# rapidshark-lipo-sensor-mk-3_2.net
KiCad netlist of a schematic drawn in EAGLE
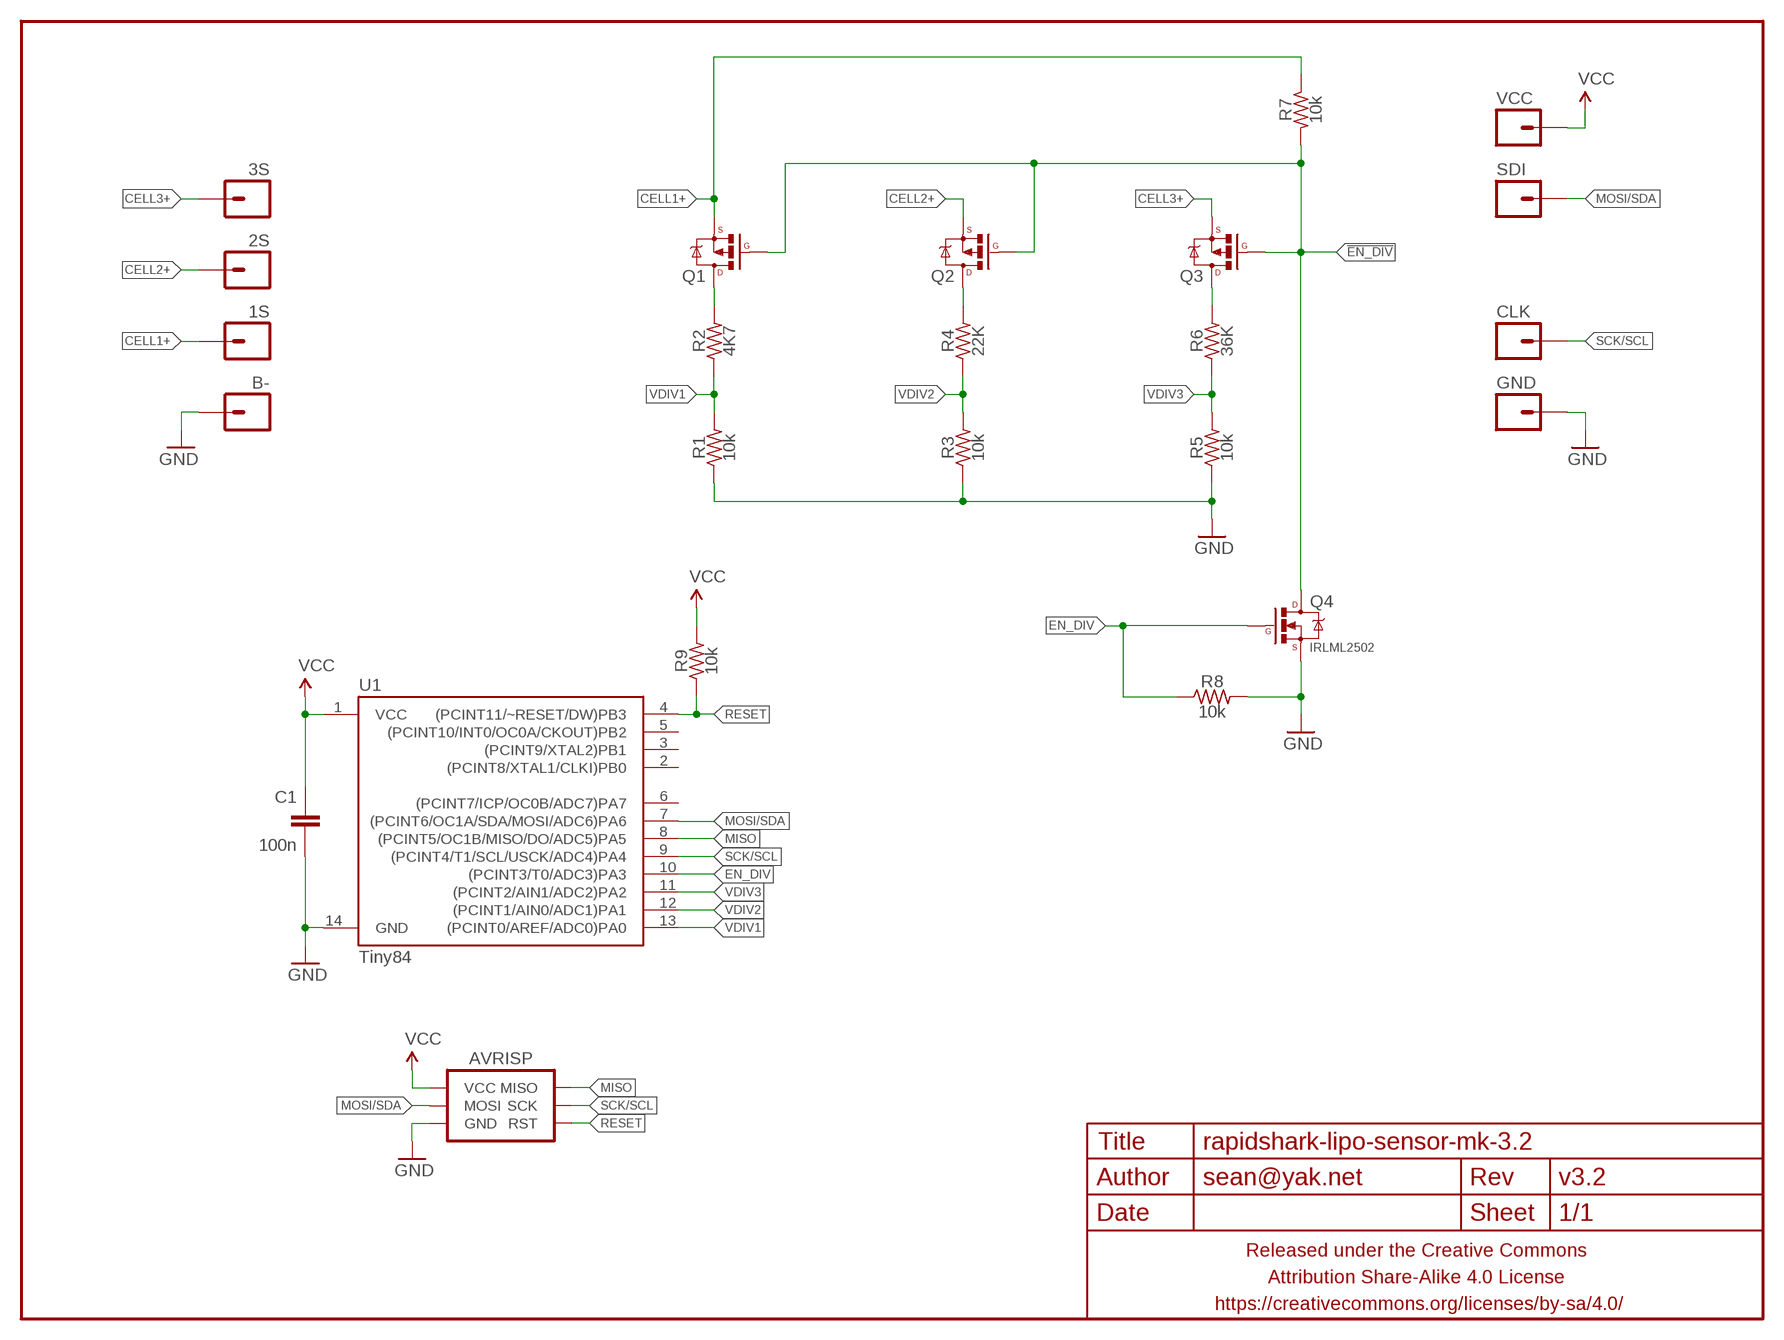
[diagram p0: schematic, sheet 1]

(export (version "E")
  (design (tool "Eeschema 10.0.6"))
  (components
    (comp (ref "1S")
      (value "M01PTH-0.9MM")
      (footprint "eagle-import:1X01-0.9MM")
      (libsource (lib "eagle-import") (part "M01PTH-0.9MM"))
    )
    (comp (ref "2S")
      (value "M01PTH-0.9MM")
      (footprint "eagle-import:1X01-0.9MM")
      (libsource (lib "eagle-import") (part "M01PTH-0.9MM"))
    )
    (comp (ref "3S")
      (value "M01PTH-0.9MM")
      (footprint "eagle-import:1X01-0.9MM")
      (libsource (lib "eagle-import") (part "M01PTH-0.9MM"))
    )
    (comp (ref "AVRISP")
      (value "AVR_SPI_PRG_6SMD_TEST_POINTS")
      (footprint "eagle-import:2X3_SMD_TEST_POINTS")
      (libsource (lib "eagle-import") (part "AVR_SPI_PRG_6SMD_TEST_POINTS"))
    )
    (comp (ref "B-")
      (value "M01PTH-0.9MM")
      (footprint "eagle-import:1X01-0.9MM")
      (libsource (lib "eagle-import") (part "M01PTH-0.9MM"))
    )
    (comp (ref "C1")
      (value "100n")
      (footprint "eagle-import:C0603-TIGHTER")
      (libsource (lib "eagle-import") (part "CAPACITOR-CERAMICC0603-TIGHTER"))
    )
    (comp (ref "CLK")
      (value "M01PTH-0.9MM")
      (footprint "eagle-import:1X01-0.9MM")
      (libsource (lib "eagle-import") (part "M01PTH-0.9MM"))
    )
    (comp (ref "FRAME1")
      (value "FRAME-LETTERNO_PACKAGE")
      (footprint "eagle-import:DUMMY")
      (fields (field (name "DESIGNER") "sean@yak.net") (field (name "VERSION") "v3.2"))
      (libsource (lib "eagle-import") (part "FRAME-LETTERNO_PACKAGE"))
    )
    (comp (ref "GND")
      (value "M01PTH-0.9MM")
      (footprint "eagle-import:1X01-0.9MM")
      (libsource (lib "eagle-import") (part "M01PTH-0.9MM"))
    )
    (comp (ref "Q1")
      (value "MOSFET-PCHANNELSOT-23")
      (footprint "eagle-import:SOT23")
      (libsource (lib "eagle-import") (part "MOSFET-PCHANNELSOT-23"))
    )
    (comp (ref "Q2")
      (value "MOSFET-PCHANNELSOT-23")
      (footprint "eagle-import:SOT23")
      (libsource (lib "eagle-import") (part "MOSFET-PCHANNELSOT-23"))
    )
    (comp (ref "Q3")
      (value "MOSFET-PCHANNELSOT-23")
      (footprint "eagle-import:SOT23")
      (libsource (lib "eagle-import") (part "MOSFET-PCHANNELSOT-23"))
    )
    (comp (ref "Q4")
      (value "IRLML2502")
      (footprint "eagle-import:SOT23")
      (libsource (lib "eagle-import") (part "MOSFET-NCHANNELIRLML2502"))
    )
    (comp (ref "R1")
      (value "10k")
      (footprint "eagle-import:R0603-TIGHTER")
      (libsource (lib "eagle-import") (part "RESISTORR0603-TIGHTER"))
    )
    (comp (ref "R2")
      (value "4K7")
      (footprint "eagle-import:R0603-TIGHTER")
      (libsource (lib "eagle-import") (part "RESISTORR0603-TIGHTER"))
    )
    (comp (ref "R3")
      (value "10k")
      (footprint "eagle-import:R0603-TIGHTER")
      (libsource (lib "eagle-import") (part "RESISTORR0603-TIGHTER"))
    )
    (comp (ref "R4")
      (value "22K")
      (footprint "eagle-import:R0603-TIGHTER")
      (libsource (lib "eagle-import") (part "RESISTORR0603-TIGHTER"))
    )
    (comp (ref "R5")
      (value "10k")
      (footprint "eagle-import:R0603-TIGHTER")
      (libsource (lib "eagle-import") (part "RESISTORR0603-TIGHTER"))
    )
    (comp (ref "R6")
      (value "36K")
      (footprint "eagle-import:R0603-TIGHTER")
      (libsource (lib "eagle-import") (part "RESISTORR0603-TIGHTER"))
    )
    (comp (ref "R7")
      (value "10k")
      (footprint "eagle-import:R0603-TIGHTER")
      (libsource (lib "eagle-import") (part "RESISTORR0603-TIGHTER"))
    )
    (comp (ref "R8")
      (value "10k")
      (footprint "eagle-import:R0603-TIGHTER")
      (libsource (lib "eagle-import") (part "RESISTORR0603-TIGHTER"))
    )
    (comp (ref "R9")
      (value "10k")
      (footprint "eagle-import:R0603-TIGHTER")
      (libsource (lib "eagle-import") (part "RESISTORR0603-TIGHTER"))
    )
    (comp (ref "SDI")
      (value "M01PTH-0.9MM")
      (footprint "eagle-import:1X01-0.9MM")
      (libsource (lib "eagle-import") (part "M01PTH-0.9MM"))
    )
    (comp (ref "U1")
      (value "Tiny84")
      (footprint "eagle-import:SO14")
      (libsource (lib "eagle-import") (part "ATTINY84"))
    )
    (comp (ref "VCC")
      (value "M01PTH-0.9MM")
      (footprint "eagle-import:1X01-0.9MM")
      (libsource (lib "eagle-import") (part "M01PTH-0.9MM"))
    )
  )
  (nets
    (net (code "1") (name "/~{EN_DIV}") (class "Default")
      (node (ref "Q1") (pin "1") (pinfunction "G_1") (pintype "passive"))
      (node (ref "Q2") (pin "1") (pinfunction "G_1") (pintype "passive"))
      (node (ref "Q3") (pin "1") (pinfunction "G_1") (pintype "passive"))
      (node (ref "Q4") (pin "3") (pinfunction "D_3") (pintype "passive"))
      (node (ref "R7") (pin "2") (pinfunction "2_2") (pintype "passive"))
    )
    (net (code "2") (name "CELL1+") (class "Default")
      (node (ref "1S") (pin "1") (pinfunction "1_1") (pintype "passive"))
      (node (ref "Q1") (pin "2") (pinfunction "S_2") (pintype "passive"))
      (node (ref "R7") (pin "1") (pinfunction "1_1") (pintype "passive"))
    )
    (net (code "3") (name "CELL2+") (class "Default")
      (node (ref "2S") (pin "1") (pinfunction "1_1") (pintype "passive"))
      (node (ref "Q2") (pin "2") (pinfunction "S_2") (pintype "passive"))
    )
    (net (code "4") (name "CELL3+") (class "Default")
      (node (ref "3S") (pin "1") (pinfunction "1_1") (pintype "passive"))
      (node (ref "Q3") (pin "2") (pinfunction "S_2") (pintype "passive"))
    )
    (net (code "5") (name "EN_DIV") (class "Default")
      (node (ref "Q4") (pin "1") (pinfunction "G_1") (pintype "passive"))
      (node (ref "R8") (pin "1") (pinfunction "1_1") (pintype "passive"))
      (node (ref "U1") (pin "10") (pinfunction "(PCINT3/T0/ADC3)PA3_10") (pintype "bidirectional"))
    )
    (net (code "6") (name "GND") (class "Default")
      (node (ref "AVRISP") (pin "6") (pinfunction "GND_6") (pintype "passive"))
      (node (ref "B-") (pin "1") (pinfunction "1_1") (pintype "passive"))
      (node (ref "C1") (pin "2") (pinfunction "2_2") (pintype "passive"))
      (node (ref "GND") (pin "1") (pinfunction "1_1") (pintype "passive"))
      (node (ref "Q4") (pin "2") (pinfunction "S_2") (pintype "passive"))
      (node (ref "R1") (pin "1") (pinfunction "1_1") (pintype "passive"))
      (node (ref "R3") (pin "1") (pinfunction "1_1") (pintype "passive"))
      (node (ref "R5") (pin "1") (pinfunction "1_1") (pintype "passive"))
      (node (ref "R8") (pin "2") (pinfunction "2_2") (pintype "passive"))
      (node (ref "U1") (pin "14") (pinfunction "GND_14") (pintype "bidirectional"))
    )
    (net (code "7") (name "MISO") (class "Default")
      (node (ref "AVRISP") (pin "1") (pinfunction "MISO_1") (pintype "passive"))
      (node (ref "U1") (pin "8") (pinfunction "(PCINT5/OC1B/MISO/DO/ADC5)PA5_8") (pintype "bidirectional"))
    )
    (net (code "8") (name "MOSI{slash}SDA") (class "Default")
      (node (ref "AVRISP") (pin "4") (pinfunction "MOSI_4") (pintype "passive"))
      (node (ref "SDI") (pin "1") (pinfunction "1_1") (pintype "passive"))
      (node (ref "U1") (pin "7") (pinfunction "(PCINT6/OC1A/SDA/MOSI/ADC6)PA6_7") (pintype "bidirectional"))
    )
    (net (code "9") (name "Net-(Q1-D)") (class "Default")
      (node (ref "Q1") (pin "3") (pinfunction "D_3") (pintype "passive"))
      (node (ref "R2") (pin "2") (pinfunction "2_2") (pintype "passive"))
    )
    (net (code "10") (name "Net-(Q2-D)") (class "Default")
      (node (ref "Q2") (pin "3") (pinfunction "D_3") (pintype "passive"))
      (node (ref "R4") (pin "2") (pinfunction "2_2") (pintype "passive"))
    )
    (net (code "11") (name "Net-(Q3-D)") (class "Default")
      (node (ref "Q3") (pin "3") (pinfunction "D_3") (pintype "passive"))
      (node (ref "R6") (pin "2") (pinfunction "2_2") (pintype "passive"))
    )
    (net (code "12") (name "RESET") (class "Default")
      (node (ref "AVRISP") (pin "5") (pinfunction "RST_5") (pintype "passive"))
      (node (ref "R9") (pin "1") (pinfunction "1_1") (pintype "passive"))
      (node (ref "U1") (pin "4") (pinfunction "(PCINT11/~{RESET/DW})PB3_4") (pintype "bidirectional"))
    )
    (net (code "13") (name "SCK{slash}SCL") (class "Default")
      (node (ref "AVRISP") (pin "3") (pinfunction "SCK_3") (pintype "passive"))
      (node (ref "CLK") (pin "1") (pinfunction "1_1") (pintype "passive"))
      (node (ref "U1") (pin "9") (pinfunction "(PCINT4/T1/SCL/USCK/ADC4)PA4_9") (pintype "bidirectional"))
    )
    (net (code "14") (name "VCC") (class "Default")
      (node (ref "AVRISP") (pin "2") (pinfunction "VCC_2") (pintype "passive"))
      (node (ref "C1") (pin "1") (pinfunction "1_1") (pintype "passive"))
      (node (ref "R9") (pin "2") (pinfunction "2_2") (pintype "passive"))
      (node (ref "U1") (pin "1") (pinfunction "VCC_1") (pintype "bidirectional"))
      (node (ref "VCC") (pin "1") (pinfunction "1_1") (pintype "passive"))
    )
    (net (code "15") (name "VDIV1") (class "Default")
      (node (ref "R1") (pin "2") (pinfunction "2_2") (pintype "passive"))
      (node (ref "R2") (pin "1") (pinfunction "1_1") (pintype "passive"))
      (node (ref "U1") (pin "13") (pinfunction "(PCINT0/AREF/ADC0)PA0_13") (pintype "bidirectional"))
    )
    (net (code "16") (name "VDIV2") (class "Default")
      (node (ref "R3") (pin "2") (pinfunction "2_2") (pintype "passive"))
      (node (ref "R4") (pin "1") (pinfunction "1_1") (pintype "passive"))
      (node (ref "U1") (pin "12") (pinfunction "(PCINT1/AIN0/ADC1)PA1_12") (pintype "bidirectional"))
    )
    (net (code "17") (name "VDIV3") (class "Default")
      (node (ref "R5") (pin "2") (pinfunction "2_2") (pintype "passive"))
      (node (ref "R6") (pin "1") (pinfunction "1_1") (pintype "passive"))
      (node (ref "U1") (pin "11") (pinfunction "(PCINT2/AIN1/ADC2)PA2_11") (pintype "bidirectional"))
    )
    (net (code "18") (name "unconnected-(U1-(PCINT7{slash}ICP{slash}OC0B{slash}ADC7)PA7-Pad6)") (class "Default")
      (node (ref "U1") (pin "6") (pinfunction "(PCINT7/ICP/OC0B/ADC7)PA7_6") (pintype "bidirectional"))
    )
    (net (code "19") (name "unconnected-(U1-(PCINT8{slash}XTAL1{slash}CLKI)PB0-Pad2)") (class "Default")
      (node (ref "U1") (pin "2") (pinfunction "(PCINT8/XTAL1/CLKI)PB0_2") (pintype "bidirectional"))
    )
    (net (code "20") (name "unconnected-(U1-(PCINT9{slash}XTAL2)PB1-Pad3)") (class "Default")
      (node (ref "U1") (pin "3") (pinfunction "(PCINT9/XTAL2)PB1_3") (pintype "bidirectional"))
    )
    (net (code "21") (name "unconnected-(U1-(PCINT10{slash}INT0{slash}OC0A{slash}CKOUT)PB2-Pad5)") (class "Default")
      (node (ref "U1") (pin "5") (pinfunction "(PCINT10/INT0/OC0A/CKOUT)PB2_5") (pintype "bidirectional"))
    )
  )
)
